# aliment_es.net
KiCad netlist of a schematic drawn in EAGLE
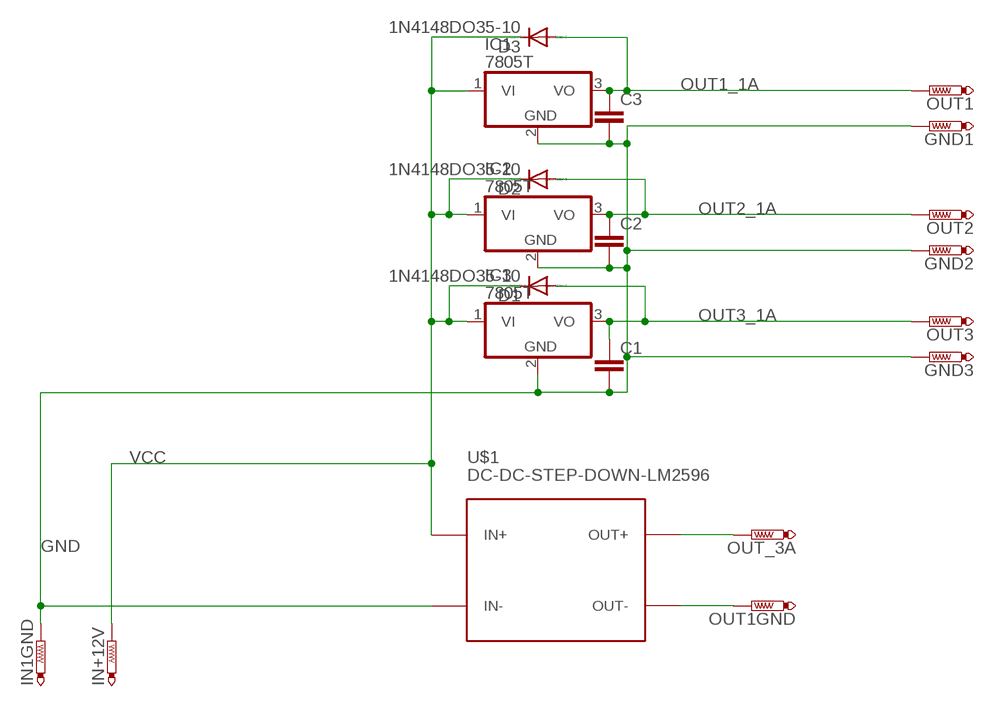
[diagram p0: schematic, sheet 1]

(export (version "E")
  (design (tool "Eeschema 10.0.6"))
  (components
    (comp (ref "C1")
      (value "C-EU050-035X075")
      (footprint "eagle-import:C050-035X075")
      (libsource (lib "eagle-import") (part "C-EU050-035X075"))
    )
    (comp (ref "C2")
      (value "C-EU050-035X075")
      (footprint "eagle-import:C050-035X075")
      (libsource (lib "eagle-import") (part "C-EU050-035X075"))
    )
    (comp (ref "C3")
      (value "C-EU050-035X075")
      (footprint "eagle-import:C050-035X075")
      (libsource (lib "eagle-import") (part "C-EU050-035X075"))
    )
    (comp (ref "D1")
      (value "1N4148DO35-10")
      (footprint "eagle-import:DO35-10")
      (libsource (lib "eagle-import") (part "1N4148DO35-10"))
    )
    (comp (ref "D2")
      (value "1N4148DO35-10")
      (footprint "eagle-import:DO35-10")
      (libsource (lib "eagle-import") (part "1N4148DO35-10"))
    )
    (comp (ref "D3")
      (value "1N4148DO35-10")
      (footprint "eagle-import:DO35-10")
      (libsource (lib "eagle-import") (part "1N4148DO35-10"))
    )
    (comp (ref "GND1")
      (value "PTR1PAD1-13Y")
      (footprint "eagle-import:P1-13Y")
      (libsource (lib "eagle-import") (part "PTR1PAD1-13Y"))
    )
    (comp (ref "GND2")
      (value "PTR1PAD1-13Y")
      (footprint "eagle-import:P1-13Y")
      (libsource (lib "eagle-import") (part "PTR1PAD1-13Y"))
    )
    (comp (ref "GND3")
      (value "PTR1PAD1-13Y")
      (footprint "eagle-import:P1-13Y")
      (libsource (lib "eagle-import") (part "PTR1PAD1-13Y"))
    )
    (comp (ref "IC1")
      (value "7805T")
      (footprint "eagle-import:TO220H")
      (libsource (lib "eagle-import") (part "78T05"))
    )
    (comp (ref "IC2")
      (value "7805T")
      (footprint "eagle-import:TO220H")
      (libsource (lib "eagle-import") (part "78T05"))
    )
    (comp (ref "IC3")
      (value "7805T")
      (footprint "eagle-import:TO220H")
      (libsource (lib "eagle-import") (part "78T05"))
    )
    (comp (ref "IN+12V")
      (value "PTR1PAD1-13Y")
      (footprint "eagle-import:P1-13Y")
      (libsource (lib "eagle-import") (part "PTR1PAD1-13Y"))
    )
    (comp (ref "IN1GND")
      (value "PTR1PAD1-13Y")
      (footprint "eagle-import:P1-13Y")
      (libsource (lib "eagle-import") (part "PTR1PAD1-13Y"))
    )
    (comp (ref "OUT1")
      (value "PTR1PAD1-13Y")
      (footprint "eagle-import:P1-13Y")
      (libsource (lib "eagle-import") (part "PTR1PAD1-13Y"))
    )
    (comp (ref "OUT1GND")
      (value "PTR1PAD1-13Y")
      (footprint "eagle-import:P1-13Y")
      (libsource (lib "eagle-import") (part "PTR1PAD1-13Y"))
    )
    (comp (ref "OUT2")
      (value "PTR1PAD1-13Y")
      (footprint "eagle-import:P1-13Y")
      (libsource (lib "eagle-import") (part "PTR1PAD1-13Y"))
    )
    (comp (ref "OUT3")
      (value "PTR1PAD1-13Y")
      (footprint "eagle-import:P1-13Y")
      (libsource (lib "eagle-import") (part "PTR1PAD1-13Y"))
    )
    (comp (ref "OUT_3A")
      (value "PTR1PAD1-13Y")
      (footprint "eagle-import:P1-13Y")
      (libsource (lib "eagle-import") (part "PTR1PAD1-13Y"))
    )
    (comp (ref "U$1")
      (value "DC-DC-STEP-DOWN-LM2596")
      (footprint "eagle-import:DC-DC-STEP-DOWN-LM2596")
      (libsource (lib "eagle-import") (part "DC-DC-STEP-DOWN-LM2596"))
    )
  )
  (nets
    (net (code "1") (name "/GND") (class "Default")
      (node (ref "C1") (pin "2") (pinfunction "2_2") (pintype "passive"))
      (node (ref "C2") (pin "2") (pinfunction "2_2") (pintype "passive"))
      (node (ref "C3") (pin "2") (pinfunction "2_2") (pintype "passive"))
      (node (ref "GND1") (pin "TP") (pinfunction "TP_TP") (pintype "input"))
      (node (ref "GND2") (pin "TP") (pinfunction "TP_TP") (pintype "input"))
      (node (ref "GND3") (pin "TP") (pinfunction "TP_TP") (pintype "input"))
      (node (ref "IC1") (pin "2") (pinfunction "GND_2") (pintype "passive"))
      (node (ref "IC2") (pin "2") (pinfunction "GND_2") (pintype "passive"))
      (node (ref "IC3") (pin "2") (pinfunction "GND_2") (pintype "passive"))
      (node (ref "IN1GND") (pin "TP") (pinfunction "TP_TP") (pintype "input"))
      (node (ref "U$1") (pin "IN-") (pinfunction "IN-_IN-") (pintype "bidirectional"))
    )
    (net (code "2") (name "/OUT1_1A") (class "Default")
      (node (ref "C3") (pin "1") (pinfunction "1_1") (pintype "passive"))
      (node (ref "D3") (pin "A") (pinfunction "A_A") (pintype "passive"))
      (node (ref "IC1") (pin "3") (pinfunction "VO_3") (pintype "passive"))
      (node (ref "OUT1") (pin "TP") (pinfunction "TP_TP") (pintype "input"))
    )
    (net (code "3") (name "/OUT2_1A") (class "Default")
      (node (ref "C2") (pin "1") (pinfunction "1_1") (pintype "passive"))
      (node (ref "D2") (pin "A") (pinfunction "A_A") (pintype "passive"))
      (node (ref "IC2") (pin "3") (pinfunction "VO_3") (pintype "passive"))
      (node (ref "OUT2") (pin "TP") (pinfunction "TP_TP") (pintype "input"))
    )
    (net (code "4") (name "/OUT3_1A") (class "Default")
      (node (ref "C1") (pin "1") (pinfunction "1_1") (pintype "passive"))
      (node (ref "D1") (pin "A") (pinfunction "A_A") (pintype "passive"))
      (node (ref "IC3") (pin "3") (pinfunction "VO_3") (pintype "passive"))
      (node (ref "OUT3") (pin "TP") (pinfunction "TP_TP") (pintype "input"))
    )
    (net (code "5") (name "/VCC") (class "Default")
      (node (ref "D1") (pin "C") (pinfunction "C_C") (pintype "passive"))
      (node (ref "D2") (pin "C") (pinfunction "C_C") (pintype "passive"))
      (node (ref "D3") (pin "C") (pinfunction "C_C") (pintype "passive"))
      (node (ref "IC1") (pin "1") (pinfunction "VI_1") (pintype "input"))
      (node (ref "IC2") (pin "1") (pinfunction "VI_1") (pintype "input"))
      (node (ref "IC3") (pin "1") (pinfunction "VI_1") (pintype "input"))
      (node (ref "IN+12V") (pin "TP") (pinfunction "TP_TP") (pintype "input"))
      (node (ref "U$1") (pin "IN+") (pinfunction "IN+_IN+") (pintype "bidirectional"))
    )
    (net (code "6") (name "Net-(OUT1GND-PadTP)") (class "Default")
      (node (ref "OUT1GND") (pin "TP") (pinfunction "TP_TP") (pintype "input"))
      (node (ref "U$1") (pin "OUT-") (pinfunction "OUT-_OUT-") (pintype "bidirectional"))
    )
    (net (code "7") (name "Net-(OUT_3A-PadTP)") (class "Default")
      (node (ref "OUT_3A") (pin "TP") (pinfunction "TP_TP") (pintype "input"))
      (node (ref "U$1") (pin "OUT+") (pinfunction "OUT+_OUT+") (pintype "bidirectional"))
    )
  )
)
